# Zio_Qwiic_Current_Sensor_INA219.net
KiCad netlist of a schematic drawn in EAGLE
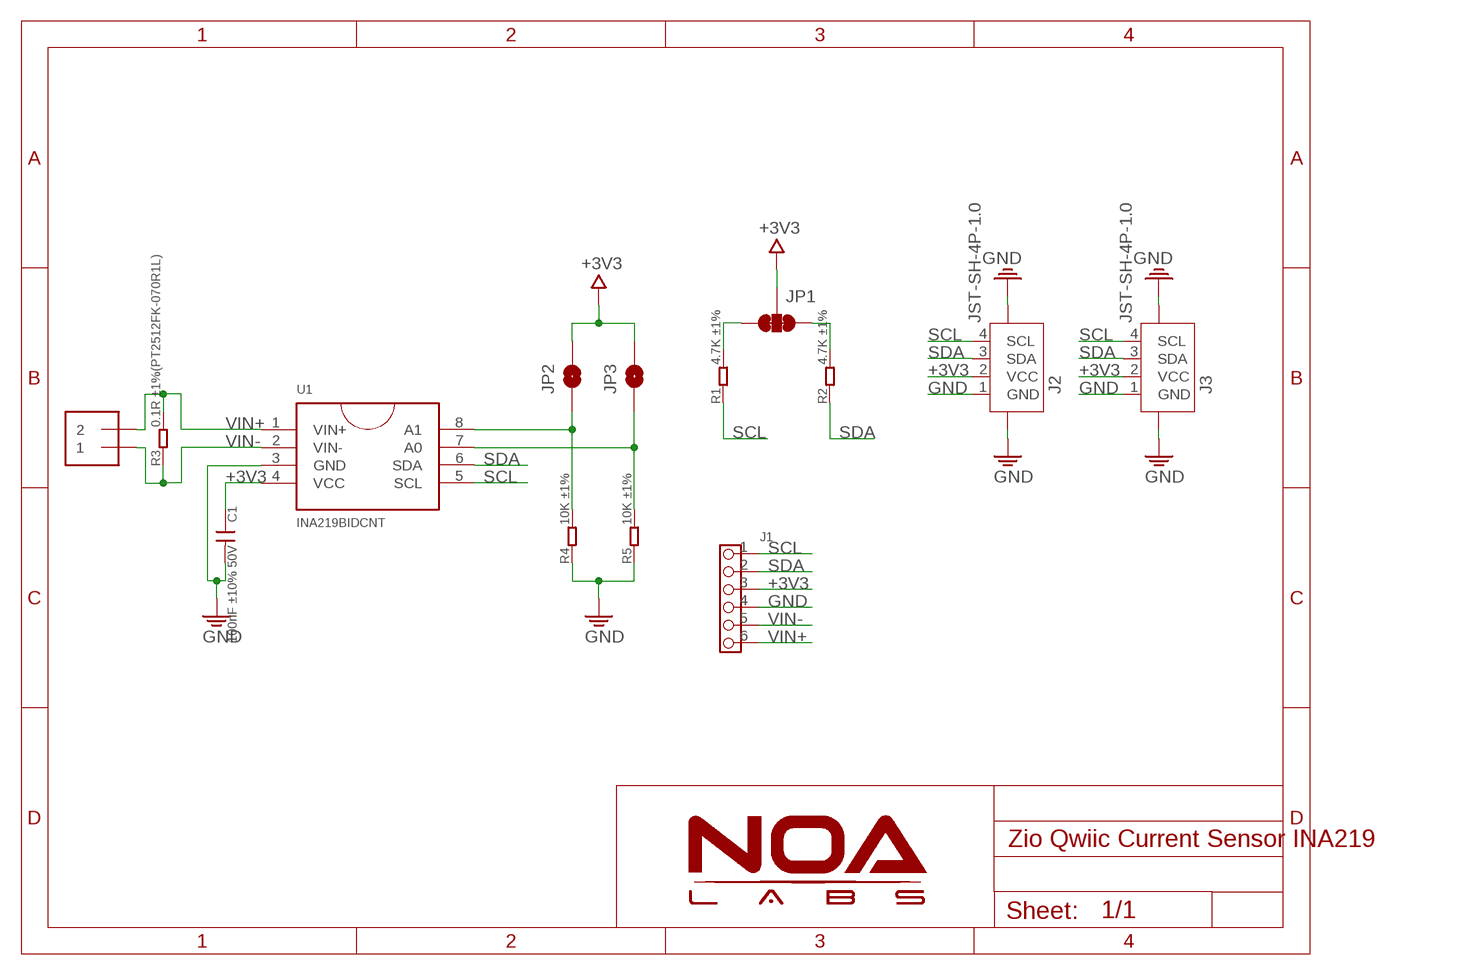
[diagram p0: schematic, sheet 1]

(export (version "E")
  (design (tool "Eeschema 10.0.6"))
  (components
    (comp (ref "C1")
      (value "100nF ±10% 50V")
      (footprint "eagle-import:C0603")
      (libsource (lib "eagle-import") (part "C-0603"))
    )
    (comp (ref "J1")
      (value "HEADER-6P-60/35MIL")
      (footprint "eagle-import:6P-2.54-60_35MIL")
      (libsource (lib "eagle-import") (part "HEADER-6P-60/35MIL"))
    )
    (comp (ref "J2")
      (value "JST-SH-4P-1.0")
      (footprint "eagle-import:JST-SH-4P")
      (libsource (lib "eagle-import") (part "JST-SH-4P-1.0"))
    )
    (comp (ref "J3")
      (value "JST-SH-4P-1.0")
      (footprint "eagle-import:JST-SH-4P")
      (libsource (lib "eagle-import") (part "JST-SH-4P-1.0"))
    )
    (comp (ref "J6")
      (value "TERMBLOCK_1X2-3.5MM")
      (footprint "eagle-import:1X2-3.5MM")
      (libsource (lib "eagle-import") (part "TERMBLOCK_1X2-3.5MM"))
    )
    (comp (ref "JP1")
      (value "SMT-JUMPER_3_2-NC_TRACE")
      (footprint "eagle-import:SMT-JUMPER_3_2-NC_TRACE")
      (libsource (lib "eagle-import") (part "SMT-JUMPER_3_2-NC_TRACE"))
    )
    (comp (ref "JP2")
      (value "JUMPER-SMT_2_NC_PASTE_NOCREM")
      (footprint "eagle-import:SMT-JUMPER_2_NC_PASTE_SILK_NOCREM")
      (libsource (lib "eagle-import") (part "JUMPER-SMT_2_NC_PASTE_NOCREM"))
    )
    (comp (ref "JP3")
      (value "JUMPER-SMT_2_NC_PASTE_NOCREM")
      (footprint "eagle-import:SMT-JUMPER_2_NC_PASTE_SILK_NOCREM")
      (libsource (lib "eagle-import") (part "JUMPER-SMT_2_NC_PASTE_NOCREM"))
    )
    (comp (ref "R1")
      (value "4.7K ±1%")
      (footprint "eagle-import:R0603")
      (libsource (lib "eagle-import") (part "R-0603"))
    )
    (comp (ref "R2")
      (value "4.7K ±1%")
      (footprint "eagle-import:R0603")
      (libsource (lib "eagle-import") (part "R-0603"))
    )
    (comp (ref "R3")
      (value "0.1R ±1%(PT2512FK-070R1L)")
      (footprint "eagle-import:R2512")
      (libsource (lib "eagle-import") (part "R-2512"))
    )
    (comp (ref "R4")
      (value "10K ±1%")
      (footprint "eagle-import:R0603")
      (libsource (lib "eagle-import") (part "R-0603"))
    )
    (comp (ref "R5")
      (value "10K ±1%")
      (footprint "eagle-import:R0603")
      (libsource (lib "eagle-import") (part "R-0603"))
    )
    (comp (ref "U1")
      (value "INA219BIDCNT")
      (footprint "eagle-import:SOT23-8")
      (libsource (lib "eagle-import") (part "INA219"))
    )
  )
  (nets
    (net (code "1") (name "+3V3") (class "Default")
      (node (ref "C1") (pin "1") (pinfunction "1_1") (pintype "passive"))
      (node (ref "J1") (pin "3") (pinfunction "3_3") (pintype "bidirectional"))
      (node (ref "J2") (pin "2") (pinfunction "VCC_2") (pintype "bidirectional"))
      (node (ref "J3") (pin "2") (pinfunction "VCC_2") (pintype "bidirectional"))
      (node (ref "JP1") (pin "2") (pinfunction "2_2") (pintype "passive"))
      (node (ref "JP2") (pin "2") (pinfunction "2_2") (pintype "passive"))
      (node (ref "JP3") (pin "2") (pinfunction "2_2") (pintype "passive"))
      (node (ref "U1") (pin "4") (pinfunction "VCC_4") (pintype "bidirectional"))
    )
    (net (code "2") (name "/SCL") (class "Default")
      (node (ref "J1") (pin "1") (pinfunction "1_1") (pintype "bidirectional"))
      (node (ref "J2") (pin "4") (pinfunction "SCL_4") (pintype "bidirectional"))
      (node (ref "J3") (pin "4") (pinfunction "SCL_4") (pintype "bidirectional"))
      (node (ref "R1") (pin "1") (pinfunction "1_1") (pintype "passive"))
      (node (ref "U1") (pin "5") (pinfunction "SCL_5") (pintype "bidirectional"))
    )
    (net (code "3") (name "/SDA") (class "Default")
      (node (ref "J1") (pin "2") (pinfunction "2_2") (pintype "bidirectional"))
      (node (ref "J2") (pin "3") (pinfunction "SDA_3") (pintype "bidirectional"))
      (node (ref "J3") (pin "3") (pinfunction "SDA_3") (pintype "bidirectional"))
      (node (ref "R2") (pin "1") (pinfunction "1_1") (pintype "passive"))
      (node (ref "U1") (pin "6") (pinfunction "SDA_6") (pintype "bidirectional"))
    )
    (net (code "4") (name "/VIN+") (class "Default")
      (node (ref "J1") (pin "6") (pinfunction "6_6") (pintype "bidirectional"))
      (node (ref "J6") (pin "2") (pinfunction "2_2") (pintype "passive"))
      (node (ref "R3") (pin "2") (pinfunction "2_2") (pintype "passive"))
      (node (ref "U1") (pin "1") (pinfunction "VIN+_1") (pintype "bidirectional"))
    )
    (net (code "5") (name "/VIN-") (class "Default")
      (node (ref "J1") (pin "5") (pinfunction "5_5") (pintype "bidirectional"))
      (node (ref "J6") (pin "1") (pinfunction "1_1") (pintype "passive"))
      (node (ref "R3") (pin "1") (pinfunction "1_1") (pintype "passive"))
      (node (ref "U1") (pin "2") (pinfunction "VIN-_2") (pintype "bidirectional"))
    )
    (net (code "6") (name "GND") (class "Default")
      (node (ref "C1") (pin "2") (pinfunction "2_2") (pintype "passive"))
      (node (ref "J1") (pin "4") (pinfunction "4_4") (pintype "bidirectional"))
      (node (ref "J2") (pin "1") (pinfunction "GND_1") (pintype "bidirectional"))
      (node (ref "J2") (pin "NC1") (pinfunction "5_NC1") (pintype "bidirectional"))
      (node (ref "J2") (pin "NC2") (pinfunction "6_NC2") (pintype "bidirectional"))
      (node (ref "J3") (pin "1") (pinfunction "GND_1") (pintype "bidirectional"))
      (node (ref "J3") (pin "NC1") (pinfunction "5_NC1") (pintype "bidirectional"))
      (node (ref "J3") (pin "NC2") (pinfunction "6_NC2") (pintype "bidirectional"))
      (node (ref "R4") (pin "1") (pinfunction "1_1") (pintype "passive"))
      (node (ref "R5") (pin "1") (pinfunction "1_1") (pintype "passive"))
      (node (ref "U1") (pin "3") (pinfunction "GND_3") (pintype "bidirectional"))
    )
    (net (code "7") (name "Net-(JP1-Pad1)") (class "Default")
      (node (ref "JP1") (pin "1") (pinfunction "1_1") (pintype "passive"))
      (node (ref "R2") (pin "2") (pinfunction "2_2") (pintype "passive"))
    )
    (net (code "8") (name "Net-(JP1-Pad3)") (class "Default")
      (node (ref "JP1") (pin "3") (pinfunction "3_3") (pintype "passive"))
      (node (ref "R1") (pin "2") (pinfunction "2_2") (pintype "passive"))
    )
    (net (code "9") (name "Net-(U1-A0)") (class "Default")
      (node (ref "JP3") (pin "1") (pinfunction "1_1") (pintype "passive"))
      (node (ref "R5") (pin "2") (pinfunction "2_2") (pintype "passive"))
      (node (ref "U1") (pin "7") (pinfunction "A0_7") (pintype "bidirectional"))
    )
    (net (code "10") (name "Net-(U1-A1)") (class "Default")
      (node (ref "JP2") (pin "1") (pinfunction "1_1") (pintype "passive"))
      (node (ref "R4") (pin "2") (pinfunction "2_2") (pintype "passive"))
      (node (ref "U1") (pin "8") (pinfunction "A1_8") (pintype "bidirectional"))
    )
  )
)
